# TouringMachineA1.net
KiCad netlist of a schematic drawn in EAGLE
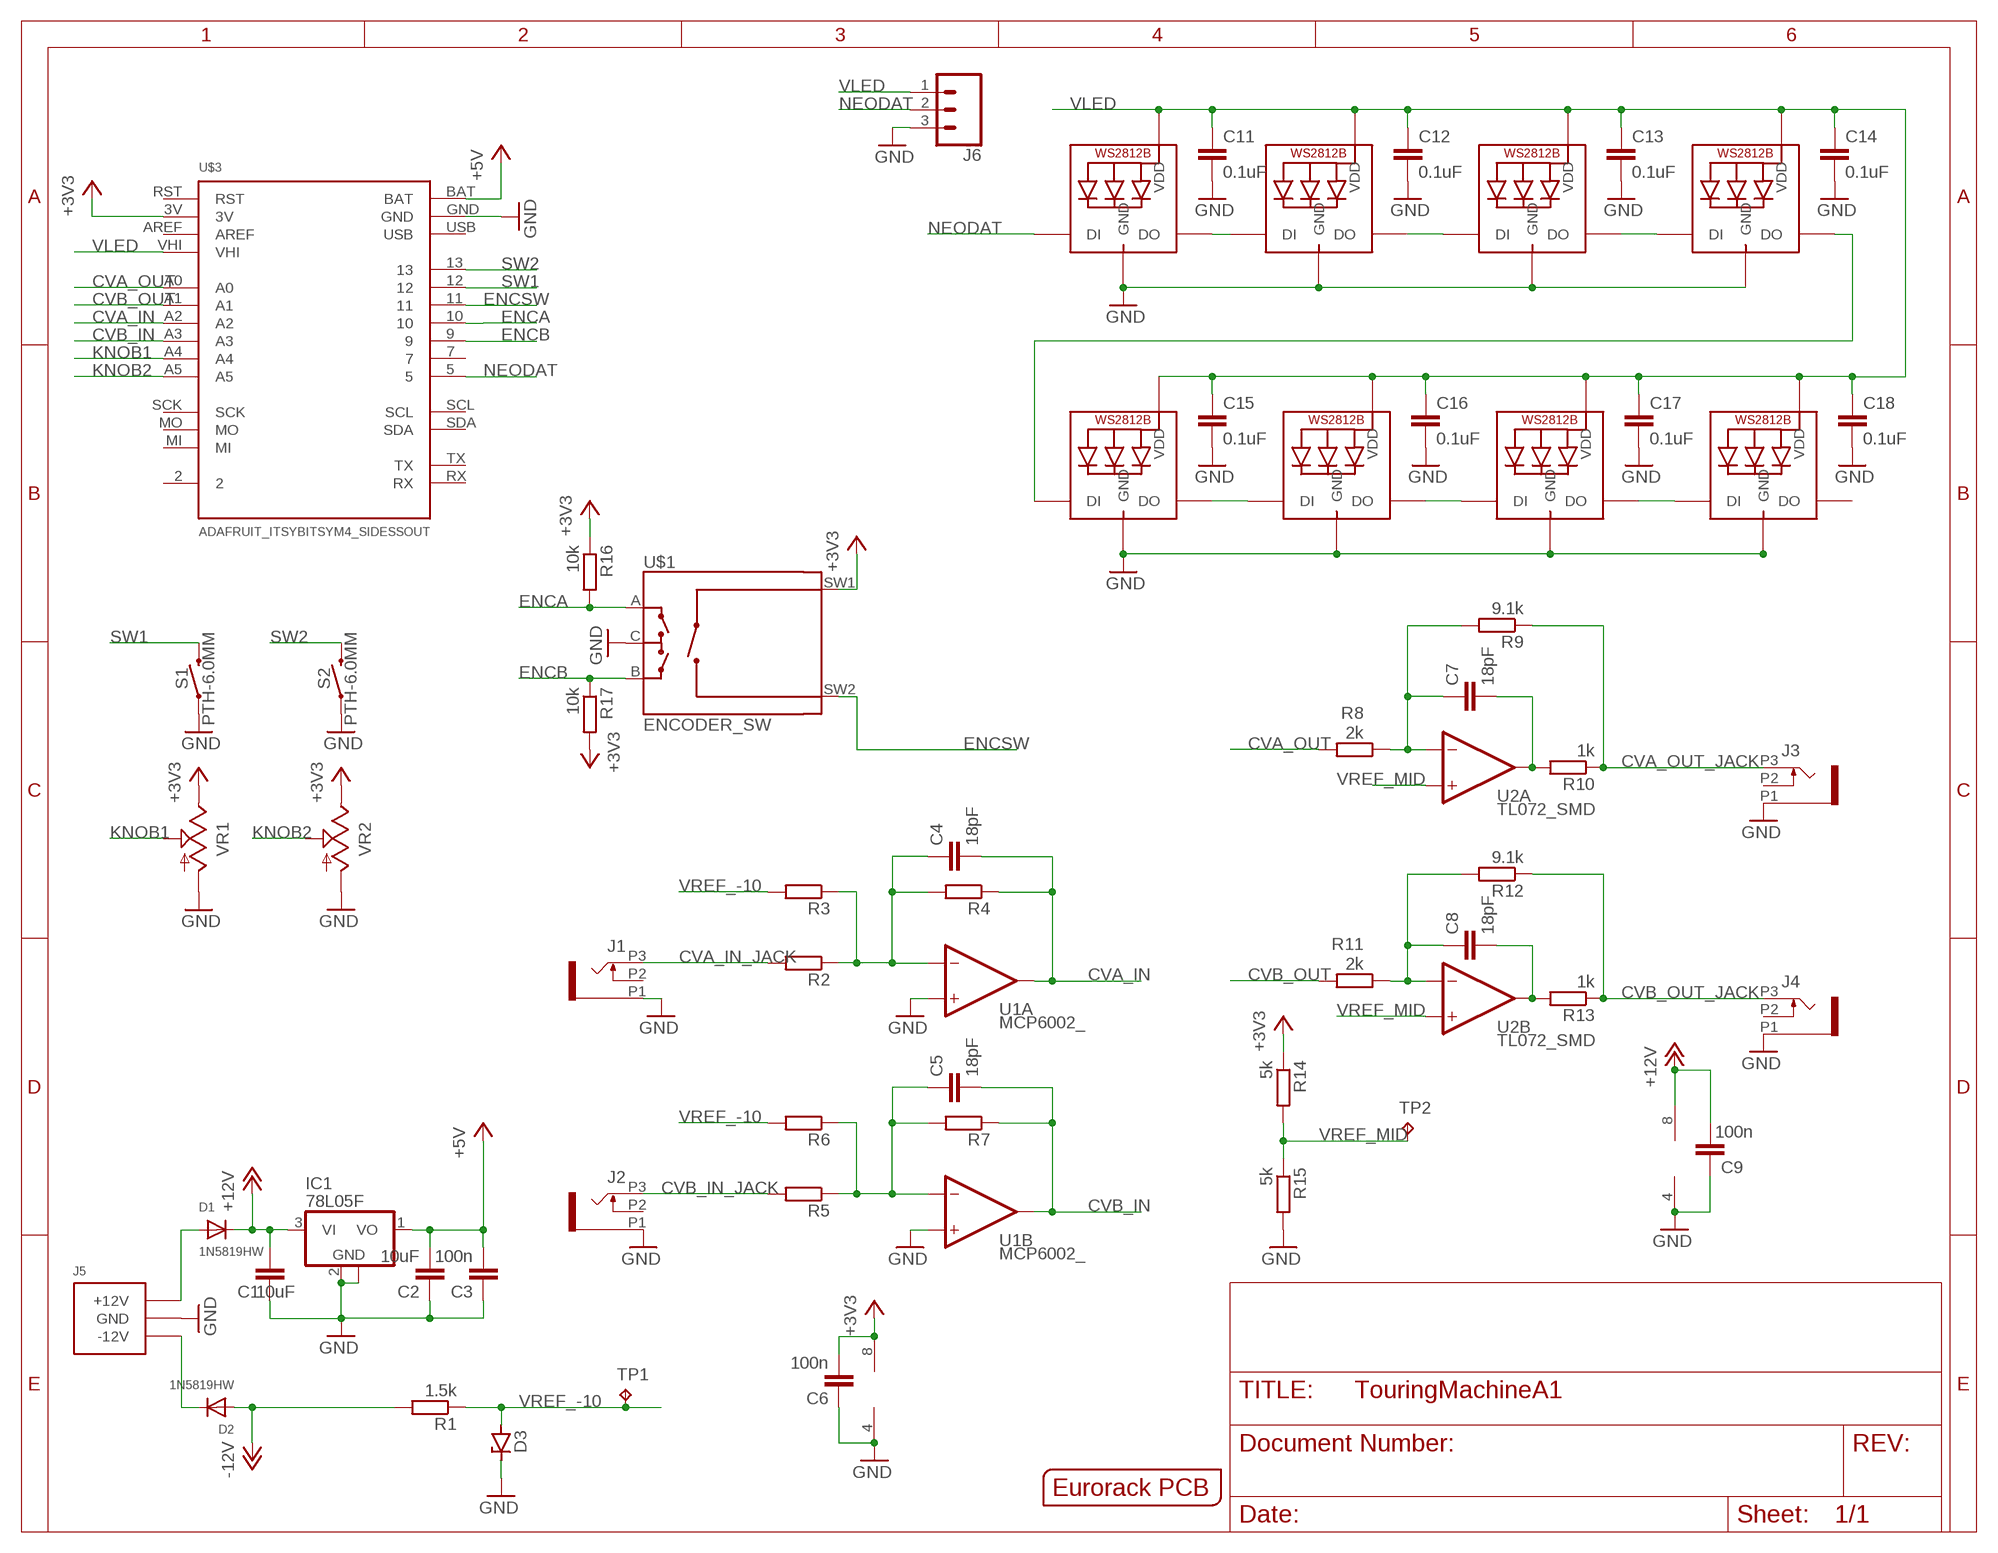
[diagram p0: schematic, sheet 1]

(export (version "E")
  (design (tool "Eeschema 10.0.6"))
  (components
    (comp (ref "C1")
      (value "10uF")
      (footprint "eagle-import:C0603")
      (libsource (lib "eagle-import") (part "C-EUC0603"))
    )
    (comp (ref "C2")
      (value "10uF")
      (footprint "eagle-import:C0603")
      (libsource (lib "eagle-import") (part "C-EUC0603"))
    )
    (comp (ref "C3")
      (value "100n")
      (footprint "eagle-import:C0603")
      (libsource (lib "eagle-import") (part "C-EUC0603"))
    )
    (comp (ref "C4")
      (value "18pF")
      (footprint "eagle-import:C0603")
      (libsource (lib "eagle-import") (part "C-EUC0603"))
    )
    (comp (ref "C5")
      (value "18pF")
      (footprint "eagle-import:C0603")
      (libsource (lib "eagle-import") (part "C-EUC0603"))
    )
    (comp (ref "C6")
      (value "100n")
      (footprint "eagle-import:C0603")
      (libsource (lib "eagle-import") (part "C-EUC0603"))
    )
    (comp (ref "C7")
      (value "18pF")
      (footprint "eagle-import:C0603")
      (libsource (lib "eagle-import") (part "C-EUC0603"))
    )
    (comp (ref "C8")
      (value "18pF")
      (footprint "eagle-import:C0603")
      (libsource (lib "eagle-import") (part "C-EUC0603"))
    )
    (comp (ref "C9")
      (value "100n")
      (footprint "eagle-import:C0603")
      (libsource (lib "eagle-import") (part "C-EUC0603"))
    )
    (comp (ref "C11")
      (value "0.1uF")
      (footprint "eagle-import:C0603")
      (libsource (lib "eagle-import") (part "C-EUC0603"))
    )
    (comp (ref "C12")
      (value "0.1uF")
      (footprint "eagle-import:C0603")
      (libsource (lib "eagle-import") (part "C-EUC0603"))
    )
    (comp (ref "C13")
      (value "0.1uF")
      (footprint "eagle-import:C0603")
      (libsource (lib "eagle-import") (part "C-EUC0603"))
    )
    (comp (ref "C14")
      (value "0.1uF")
      (footprint "eagle-import:C0603")
      (libsource (lib "eagle-import") (part "C-EUC0603"))
    )
    (comp (ref "C15")
      (value "0.1uF")
      (footprint "eagle-import:C0603")
      (libsource (lib "eagle-import") (part "C-EUC0603"))
    )
    (comp (ref "C16")
      (value "0.1uF")
      (footprint "eagle-import:C0603")
      (libsource (lib "eagle-import") (part "C-EUC0603"))
    )
    (comp (ref "C17")
      (value "0.1uF")
      (footprint "eagle-import:C0603")
      (libsource (lib "eagle-import") (part "C-EUC0603"))
    )
    (comp (ref "C18")
      (value "0.1uF")
      (footprint "eagle-import:C0603")
      (libsource (lib "eagle-import") (part "C-EUC0603"))
    )
    (comp (ref "D1")
      (value "1N5819HW")
      (footprint "eagle-import:SOD-123")
      (libsource (lib "eagle-import") (part "DIODESOD-123"))
    )
    (comp (ref "D2")
      (value "1N5819HW")
      (footprint "eagle-import:SOD-123")
      (libsource (lib "eagle-import") (part "DIODESOD-123"))
    )
    (comp (ref "D3")
      (value "ZENER-DIODESOT23")
      (footprint "eagle-import:SOT23")
      (libsource (lib "eagle-import") (part "ZENER-DIODESOT23"))
    )
    (comp (ref "IC1")
      (value "78L05F")
      (footprint "eagle-import:SOT89")
      (libsource (lib "eagle-import") (part "78LF05"))
    )
    (comp (ref "J1")
      (value "PJ301_THONKICONN6")
      (footprint "eagle-import:WQP_PJ_301M6")
      (libsource (lib "eagle-import") (part "PJ301_THONKICONN6"))
    )
    (comp (ref "J2")
      (value "PJ301_THONKICONN6")
      (footprint "eagle-import:WQP_PJ_301M6")
      (libsource (lib "eagle-import") (part "PJ301_THONKICONN6"))
    )
    (comp (ref "J3")
      (value "PJ301_THONKICONN6")
      (footprint "eagle-import:WQP_PJ_301M6")
      (libsource (lib "eagle-import") (part "PJ301_THONKICONN6"))
    )
    (comp (ref "J4")
      (value "PJ301_THONKICONN6")
      (footprint "eagle-import:WQP_PJ_301M6")
      (libsource (lib "eagle-import") (part "PJ301_THONKICONN6"))
    )
    (comp (ref "J5")
      (value "POWER_SIMPLE10-OTHERSIDE")
      (footprint "eagle-import:POWER_10_LABELSOTHERSIDE")
      (libsource (lib "eagle-import") (part "POWER_SIMPLE10-OTHERSIDE"))
    )
    (comp (ref "J6")
      (value "CONN_03")
      (footprint "eagle-import:1X03")
      (libsource (lib "eagle-import") (part "CONN_03"))
    )
    (comp (ref "LED1")
      (value "WS2812B5050")
      (footprint "eagle-import:WS2812B")
      (libsource (lib "eagle-import") (part "WS2812B5050"))
    )
    (comp (ref "LED2")
      (value "WS2812B5050")
      (footprint "eagle-import:WS2812B")
      (libsource (lib "eagle-import") (part "WS2812B5050"))
    )
    (comp (ref "LED3")
      (value "WS2812B5050")
      (footprint "eagle-import:WS2812B")
      (libsource (lib "eagle-import") (part "WS2812B5050"))
    )
    (comp (ref "LED4")
      (value "WS2812B5050")
      (footprint "eagle-import:WS2812B")
      (libsource (lib "eagle-import") (part "WS2812B5050"))
    )
    (comp (ref "LED5")
      (value "WS2812B5050")
      (footprint "eagle-import:WS2812B")
      (libsource (lib "eagle-import") (part "WS2812B5050"))
    )
    (comp (ref "LED6")
      (value "WS2812B5050")
      (footprint "eagle-import:WS2812B")
      (libsource (lib "eagle-import") (part "WS2812B5050"))
    )
    (comp (ref "LED7")
      (value "WS2812B5050")
      (footprint "eagle-import:WS2812B")
      (libsource (lib "eagle-import") (part "WS2812B5050"))
    )
    (comp (ref "LED8")
      (value "WS2812B5050")
      (footprint "eagle-import:WS2812B")
      (libsource (lib "eagle-import") (part "WS2812B5050"))
    )
    (comp (ref "PCB1")
      (value "EURORACK_PCB6HP")
      (footprint "eagle-import:EURORACK6HPPCB")
      (libsource (lib "eagle-import") (part "EURORACK_PCB6HP"))
    )
    (comp (ref "R1")
      (value "1.5k")
      (footprint "eagle-import:R0603")
      (libsource (lib "eagle-import") (part "R-EU_R0603"))
    )
    (comp (ref "R2")
      (value "R-EU_R0603")
      (footprint "eagle-import:R0603")
      (libsource (lib "eagle-import") (part "R-EU_R0603"))
    )
    (comp (ref "R3")
      (value "R-EU_R0603")
      (footprint "eagle-import:R0603")
      (libsource (lib "eagle-import") (part "R-EU_R0603"))
    )
    (comp (ref "R4")
      (value "R-EU_R0603")
      (footprint "eagle-import:R0603")
      (libsource (lib "eagle-import") (part "R-EU_R0603"))
    )
    (comp (ref "R5")
      (value "R-EU_R0603")
      (footprint "eagle-import:R0603")
      (libsource (lib "eagle-import") (part "R-EU_R0603"))
    )
    (comp (ref "R6")
      (value "R-EU_R0603")
      (footprint "eagle-import:R0603")
      (libsource (lib "eagle-import") (part "R-EU_R0603"))
    )
    (comp (ref "R7")
      (value "R-EU_R0603")
      (footprint "eagle-import:R0603")
      (libsource (lib "eagle-import") (part "R-EU_R0603"))
    )
    (comp (ref "R8")
      (value "2k")
      (footprint "eagle-import:R0603")
      (libsource (lib "eagle-import") (part "R-EU_R0603"))
    )
    (comp (ref "R9")
      (value "9.1k")
      (footprint "eagle-import:R0603")
      (libsource (lib "eagle-import") (part "R-EU_R0603"))
    )
    (comp (ref "R10")
      (value "1k")
      (footprint "eagle-import:R0603")
      (libsource (lib "eagle-import") (part "R-EU_R0603"))
    )
    (comp (ref "R11")
      (value "2k")
      (footprint "eagle-import:R0603")
      (libsource (lib "eagle-import") (part "R-EU_R0603"))
    )
    (comp (ref "R12")
      (value "9.1k")
      (footprint "eagle-import:R0603")
      (libsource (lib "eagle-import") (part "R-EU_R0603"))
    )
    (comp (ref "R13")
      (value "1k")
      (footprint "eagle-import:R0603")
      (libsource (lib "eagle-import") (part "R-EU_R0603"))
    )
    (comp (ref "R14")
      (value "5k")
      (footprint "eagle-import:R0603")
      (libsource (lib "eagle-import") (part "R-EU_R0603"))
    )
    (comp (ref "R15")
      (value "5k")
      (footprint "eagle-import:R0603")
      (libsource (lib "eagle-import") (part "R-EU_R0603"))
    )
    (comp (ref "R16")
      (value "10k")
      (footprint "eagle-import:R0603")
      (libsource (lib "eagle-import") (part "R-EU_R0603"))
    )
    (comp (ref "R17")
      (value "10k")
      (footprint "eagle-import:R0603")
      (libsource (lib "eagle-import") (part "R-EU_R0603"))
    )
    (comp (ref "S1")
      (value "PTH-6.0MM")
      (footprint "eagle-import:TACTILE_SWITCH_PTH_6.0MM")
      (libsource (lib "eagle-import") (part "MOMENTARY-SWITCH-SPST-PTH-6.0MM"))
    )
    (comp (ref "S2")
      (value "PTH-6.0MM")
      (footprint "eagle-import:TACTILE_SWITCH_PTH_6.0MM")
      (libsource (lib "eagle-import") (part "MOMENTARY-SWITCH-SPST-PTH-6.0MM"))
    )
    (comp (ref "TP1")
      (value "TPTP15R")
      (footprint "eagle-import:TP15R")
      (libsource (lib "eagle-import") (part "TPTP15R"))
    )
    (comp (ref "TP2")
      (value "TPTP15R")
      (footprint "eagle-import:TP15R")
      (libsource (lib "eagle-import") (part "TPTP15R"))
    )
    (comp (ref "U$1")
      (value "ENCODER_SW")
      (footprint "eagle-import:ENCODER_SW")
      (libsource (lib "eagle-import") (part "ENCODER_SW"))
    )
    (comp (ref "U$3")
      (value "ADAFRUIT_ITSYBITSYM4_SIDESSOUT")
      (footprint "eagle-import:ADAFRUIT_ITSYBITSYM4_SIDESOUT")
      (libsource (lib "eagle-import") (part "ADAFRUIT_ITSYBITSYM4_SIDESSOUT"))
    )
    (comp (ref "U1")
      (value "MCP6002_")
      (footprint "eagle-import:SO08")
      (libsource (lib "eagle-import") (part "MCP6002_"))
    )
    (comp (ref "U2")
      (value "TL072_SMD")
      (footprint "eagle-import:SO08")
      (libsource (lib "eagle-import") (part "TL072_SMD"))
    )
    (comp (ref "VR1")
      (value "9MM_SNAP-IN_POT_")
      (footprint "eagle-import:9MM_SNAP-IN_POT")
      (libsource (lib "eagle-import") (part "9MM_SNAP-IN_POT_"))
    )
    (comp (ref "VR2")
      (value "9MM_SNAP-IN_POT_")
      (footprint "eagle-import:9MM_SNAP-IN_POT")
      (libsource (lib "eagle-import") (part "9MM_SNAP-IN_POT_"))
    )
  )
  (nets
    (net (code "1") (name "+3V3") (class "Default")
      (node (ref "C6") (pin "2") (pinfunction "2_2") (pintype "passive"))
      (node (ref "R14") (pin "1") (pinfunction "1_1") (pintype "passive"))
      (node (ref "R16") (pin "1") (pinfunction "1_1") (pintype "passive"))
      (node (ref "R17") (pin "2") (pinfunction "2_2") (pintype "passive"))
      (node (ref "U$1") (pin "SW1") (pinfunction "SW1_SW1") (pintype "passive"))
      (node (ref "U$3") (pin "3V") (pinfunction "3V_3V") (pintype "bidirectional"))
      (node (ref "U1") (pin "8") (pinfunction "V+_8") (pintype "power_in"))
      (node (ref "VR1") (pin "3") (pinfunction "E_3") (pintype "passive"))
      (node (ref "VR2") (pin "3") (pinfunction "E_3") (pintype "passive"))
    )
    (net (code "2") (name "+5V") (class "Default")
      (node (ref "C2") (pin "2") (pinfunction "2_2") (pintype "passive"))
      (node (ref "C3") (pin "2") (pinfunction "2_2") (pintype "passive"))
      (node (ref "IC1") (pin "1") (pinfunction "VO_1") (pintype "passive"))
      (node (ref "U$3") (pin "BAT") (pinfunction "BAT_BAT") (pintype "bidirectional"))
    )
    (net (code "3") (name "+12V") (class "Default")
      (node (ref "C1") (pin "2") (pinfunction "2_2") (pintype "passive"))
      (node (ref "C9") (pin "2") (pinfunction "2_2") (pintype "passive"))
      (node (ref "D1") (pin "C") (pinfunction "C_C") (pintype "passive"))
      (node (ref "IC1") (pin "3") (pinfunction "VI_3") (pintype "input"))
      (node (ref "U2") (pin "8") (pinfunction "V+_8") (pintype "power_in"))
    )
    (net (code "4") (name "-12V") (class "Default")
      (node (ref "D2") (pin "A") (pinfunction "A_A") (pintype "passive"))
      (node (ref "R1") (pin "2") (pinfunction "2_2") (pintype "passive"))
    )
    (net (code "5") (name "/CVA_IN") (class "Default")
      (node (ref "C4") (pin "2") (pinfunction "2_2") (pintype "passive"))
      (node (ref "R4") (pin "1") (pinfunction "1_1") (pintype "passive"))
      (node (ref "U$3") (pin "A2") (pinfunction "A2_A2") (pintype "bidirectional"))
      (node (ref "U1") (pin "1") (pinfunction "OUT_1") (pintype "output"))
    )
    (net (code "6") (name "/CVA_IN_JACK") (class "Default")
      (node (ref "J1") (pin "P3") (pinfunction "3_P3") (pintype "passive"))
      (node (ref "R2") (pin "2") (pinfunction "2_2") (pintype "passive"))
    )
    (net (code "7") (name "/CVA_OUT") (class "Default")
      (node (ref "R8") (pin "2") (pinfunction "2_2") (pintype "passive"))
      (node (ref "U$3") (pin "A0") (pinfunction "A0_A0") (pintype "bidirectional"))
    )
    (net (code "8") (name "/CVA_OUT_JACK") (class "Default")
      (node (ref "J3") (pin "P3") (pinfunction "3_P3") (pintype "passive"))
      (node (ref "R10") (pin "1") (pinfunction "1_1") (pintype "passive"))
      (node (ref "R9") (pin "1") (pinfunction "1_1") (pintype "passive"))
    )
    (net (code "9") (name "/CVB_IN") (class "Default")
      (node (ref "C5") (pin "2") (pinfunction "2_2") (pintype "passive"))
      (node (ref "R7") (pin "1") (pinfunction "1_1") (pintype "passive"))
      (node (ref "U$3") (pin "A3") (pinfunction "A3_A3") (pintype "bidirectional"))
      (node (ref "U1") (pin "7") (pinfunction "OUT_7") (pintype "output"))
    )
    (net (code "10") (name "/CVB_IN_JACK") (class "Default")
      (node (ref "J2") (pin "P3") (pinfunction "3_P3") (pintype "passive"))
      (node (ref "R5") (pin "2") (pinfunction "2_2") (pintype "passive"))
    )
    (net (code "11") (name "/CVB_OUT") (class "Default")
      (node (ref "R11") (pin "2") (pinfunction "2_2") (pintype "passive"))
      (node (ref "U$3") (pin "A1") (pinfunction "A1_A1") (pintype "bidirectional"))
    )
    (net (code "12") (name "/CVB_OUT_JACK") (class "Default")
      (node (ref "J4") (pin "P3") (pinfunction "3_P3") (pintype "passive"))
      (node (ref "R12") (pin "1") (pinfunction "1_1") (pintype "passive"))
      (node (ref "R13") (pin "1") (pinfunction "1_1") (pintype "passive"))
    )
    (net (code "13") (name "/ENCA") (class "Default")
      (node (ref "R16") (pin "2") (pinfunction "2_2") (pintype "passive"))
      (node (ref "U$1") (pin "A") (pinfunction "A_A") (pintype "bidirectional"))
      (node (ref "U$3") (pin "10") (pinfunction "10_10") (pintype "bidirectional"))
    )
    (net (code "14") (name "/ENCB") (class "Default")
      (node (ref "R17") (pin "1") (pinfunction "1_1") (pintype "passive"))
      (node (ref "U$1") (pin "B") (pinfunction "B_B") (pintype "bidirectional"))
      (node (ref "U$3") (pin "9") (pinfunction "9_9") (pintype "bidirectional"))
    )
    (net (code "15") (name "/ENCSW") (class "Default")
      (node (ref "U$1") (pin "SW2") (pinfunction "SW2_SW2") (pintype "passive"))
      (node (ref "U$3") (pin "11") (pinfunction "11_11") (pintype "bidirectional"))
    )
    (net (code "16") (name "/KNOB1") (class "Default")
      (node (ref "U$3") (pin "A4") (pinfunction "A4_A4") (pintype "bidirectional"))
      (node (ref "VR1") (pin "2") (pinfunction "S_2") (pintype "passive"))
    )
    (net (code "17") (name "/KNOB2") (class "Default")
      (node (ref "U$3") (pin "A5") (pinfunction "A5_A5") (pintype "bidirectional"))
      (node (ref "VR2") (pin "2") (pinfunction "S_2") (pintype "passive"))
    )
    (net (code "18") (name "/NEODAT") (class "Default")
      (node (ref "J6") (pin "2") (pinfunction "2_2") (pintype "passive"))
      (node (ref "LED1") (pin "4-DIN") (pinfunction "DI_4-DIN") (pintype "input"))
      (node (ref "U$3") (pin "5") (pinfunction "5_5") (pintype "bidirectional"))
    )
    (net (code "19") (name "/SW1") (class "Default")
      (node (ref "S1") (pin "3") (pinfunction "2_3") (pintype "passive"))
      (node (ref "U$3") (pin "12") (pinfunction "12_12") (pintype "bidirectional"))
    )
    (net (code "20") (name "/SW2") (class "Default")
      (node (ref "S2") (pin "3") (pinfunction "2_3") (pintype "passive"))
      (node (ref "U$3") (pin "13") (pinfunction "13_13") (pintype "bidirectional"))
    )
    (net (code "21") (name "/VLED") (class "Default")
      (node (ref "C11") (pin "1") (pinfunction "1_1") (pintype "passive"))
      (node (ref "C12") (pin "1") (pinfunction "1_1") (pintype "passive"))
      (node (ref "C13") (pin "1") (pinfunction "1_1") (pintype "passive"))
      (node (ref "C14") (pin "1") (pinfunction "1_1") (pintype "passive"))
      (node (ref "C15") (pin "1") (pinfunction "1_1") (pintype "passive"))
      (node (ref "C16") (pin "1") (pinfunction "1_1") (pintype "passive"))
      (node (ref "C17") (pin "1") (pinfunction "1_1") (pintype "passive"))
      (node (ref "C18") (pin "1") (pinfunction "1_1") (pintype "passive"))
      (node (ref "J6") (pin "1") (pinfunction "1_1") (pintype "passive"))
      (node (ref "LED1") (pin "1-VDD") (pinfunction "VDD_1-VDD") (pintype "power_in"))
      (node (ref "LED2") (pin "1-VDD") (pinfunction "VDD_1-VDD") (pintype "power_in"))
      (node (ref "LED3") (pin "1-VDD") (pinfunction "VDD_1-VDD") (pintype "power_in"))
      (node (ref "LED4") (pin "1-VDD") (pinfunction "VDD_1-VDD") (pintype "power_in"))
      (node (ref "LED5") (pin "1-VDD") (pinfunction "VDD_1-VDD") (pintype "power_in"))
      (node (ref "LED6") (pin "1-VDD") (pinfunction "VDD_1-VDD") (pintype "power_in"))
      (node (ref "LED7") (pin "1-VDD") (pinfunction "VDD_1-VDD") (pintype "power_in"))
      (node (ref "LED8") (pin "1-VDD") (pinfunction "VDD_1-VDD") (pintype "power_in"))
      (node (ref "U$3") (pin "VHI") (pinfunction "VHI_VHI") (pintype "bidirectional"))
    )
    (net (code "22") (name "/VREF_-10") (class "Default")
      (node (ref "D3") (pin "1") (pinfunction "A_1") (pintype "passive"))
      (node (ref "R1") (pin "1") (pinfunction "1_1") (pintype "passive"))
      (node (ref "R3") (pin "2") (pinfunction "2_2") (pintype "passive"))
      (node (ref "R6") (pin "2") (pinfunction "2_2") (pintype "passive"))
      (node (ref "TP1") (pin "TP") (pinfunction "TP_TP") (pintype "input"))
    )
    (net (code "23") (name "/VREF_MID") (class "Default")
      (node (ref "R14") (pin "2") (pinfunction "2_2") (pintype "passive"))
      (node (ref "R15") (pin "1") (pinfunction "1_1") (pintype "passive"))
      (node (ref "TP2") (pin "TP") (pinfunction "TP_TP") (pintype "input"))
      (node (ref "U2") (pin "3") (pinfunction "+IN_3") (pintype "input"))
      (node (ref "U2") (pin "5") (pinfunction "+IN_5") (pintype "input"))
    )
    (net (code "24") (name "GND") (class "Default")
      (node (ref "C1") (pin "1") (pinfunction "1_1") (pintype "passive"))
      (node (ref "C11") (pin "2") (pinfunction "2_2") (pintype "passive"))
      (node (ref "C12") (pin "2") (pinfunction "2_2") (pintype "passive"))
      (node (ref "C13") (pin "2") (pinfunction "2_2") (pintype "passive"))
      (node (ref "C14") (pin "2") (pinfunction "2_2") (pintype "passive"))
      (node (ref "C15") (pin "2") (pinfunction "2_2") (pintype "passive"))
      (node (ref "C16") (pin "2") (pinfunction "2_2") (pintype "passive"))
      (node (ref "C17") (pin "2") (pinfunction "2_2") (pintype "passive"))
      (node (ref "C18") (pin "2") (pinfunction "2_2") (pintype "passive"))
      (node (ref "C2") (pin "1") (pinfunction "1_1") (pintype "passive"))
      (node (ref "C3") (pin "1") (pinfunction "1_1") (pintype "passive"))
      (node (ref "C6") (pin "1") (pinfunction "1_1") (pintype "passive"))
      (node (ref "C9") (pin "1") (pinfunction "1_1") (pintype "passive"))
      (node (ref "D3") (pin "3") (pinfunction "C_3") (pintype "passive"))
      (node (ref "IC1") (pin "2") (pinfunction "GND_2") (pintype "passive"))
      (node (ref "IC1") (pin "2@1") (pinfunction "GND_2@1") (pintype "passive"))
      (node (ref "J1") (pin "P1") (pinfunction "1_P1") (pintype "passive"))
      (node (ref "J2") (pin "P1") (pinfunction "1_P1") (pintype "passive"))
      (node (ref "J3") (pin "P1") (pinfunction "1_P1") (pintype "passive"))
      (node (ref "J4") (pin "P1") (pinfunction "1_P1") (pintype "passive"))
      (node (ref "J5") (pin "3") (pinfunction "GND_3") (pintype "bidirectional"))
      (node (ref "J5") (pin "4") (pinfunction "GND_4") (pintype "bidirectional"))
      (node (ref "J5") (pin "5") (pinfunction "GND_5") (pintype "bidirectional"))
      (node (ref "J5") (pin "6") (pinfunction "GND_6") (pintype "bidirectional"))
      (node (ref "J5") (pin "7") (pinfunction "GND_7") (pintype "bidirectional"))
      (node (ref "J5") (pin "8") (pinfunction "GND_8") (pintype "bidirectional"))
      (node (ref "J6") (pin "3") (pinfunction "3_3") (pintype "passive"))
      (node (ref "LED1") (pin "3-GND") (pinfunction "GND_3-GND") (pintype "power_in"))
      (node (ref "LED2") (pin "3-GND") (pinfunction "GND_3-GND") (pintype "power_in"))
      (node (ref "LED3") (pin "3-GND") (pinfunction "GND_3-GND") (pintype "power_in"))
      (node (ref "LED4") (pin "3-GND") (pinfunction "GND_3-GND") (pintype "power_in"))
      (node (ref "LED5") (pin "3-GND") (pinfunction "GND_3-GND") (pintype "power_in"))
      (node (ref "LED6") (pin "3-GND") (pinfunction "GND_3-GND") (pintype "power_in"))
      (node (ref "LED7") (pin "3-GND") (pinfunction "GND_3-GND") (pintype "power_in"))
      (node (ref "LED8") (pin "3-GND") (pinfunction "GND_3-GND") (pintype "power_in"))
      (node (ref "R15") (pin "2") (pinfunction "2_2") (pintype "passive"))
      (node (ref "S1") (pin "1") (pinfunction "1_1") (pintype "passive"))
      (node (ref "S2") (pin "1") (pinfunction "1_1") (pintype "passive"))
      (node (ref "U$1") (pin "C") (pinfunction "C_C") (pintype "bidirectional"))
      (node (ref "U$3") (pin "GND") (pinfunction "GND_GND") (pintype "bidirectional"))
      (node (ref "U1") (pin "3") (pinfunction "+IN_3") (pintype "input"))
      (node (ref "U1") (pin "4") (pinfunction "V-_4") (pintype "power_in"))
      (node (ref "U1") (pin "5") (pinfunction "+IN_5") (pintype "input"))
      (node (ref "U2") (pin "4") (pinfunction "V-_4") (pintype "power_in"))
      (node (ref "VR1") (pin "1") (pinfunction "A_1") (pintype "passive"))
      (node (ref "VR2") (pin "1") (pinfunction "A_1") (pintype "passive"))
    )
    (net (code "25") (name "Net-(D1-PadA)") (class "Default")
      (node (ref "D1") (pin "A") (pinfunction "A_A") (pintype "passive"))
      (node (ref "J5") (pin "10") (pinfunction "+12V_10") (pintype "bidirectional"))
      (node (ref "J5") (pin "9") (pinfunction "+12V_9") (pintype "bidirectional"))
    )
    (net (code "26") (name "Net-(D2-PadC)") (class "Default")
      (node (ref "D2") (pin "C") (pinfunction "C_C") (pintype "passive"))
      (node (ref "J5") (pin "1") (pinfunction "-12V_1") (pintype "bidirectional"))
      (node (ref "J5") (pin "2") (pinfunction "-12V_2") (pintype "bidirectional"))
    )
    (net (code "27") (name "Net-(LED1-DO)") (class "Default")
      (node (ref "LED1") (pin "2-DOUT") (pinfunction "DO_2-DOUT") (pintype "output"))
      (node (ref "LED2") (pin "4-DIN") (pinfunction "DI_4-DIN") (pintype "input"))
    )
    (net (code "28") (name "Net-(LED2-DO)") (class "Default")
      (node (ref "LED2") (pin "2-DOUT") (pinfunction "DO_2-DOUT") (pintype "output"))
      (node (ref "LED3") (pin "4-DIN") (pinfunction "DI_4-DIN") (pintype "input"))
    )
    (net (code "29") (name "Net-(LED3-DO)") (class "Default")
      (node (ref "LED3") (pin "2-DOUT") (pinfunction "DO_2-DOUT") (pintype "output"))
      (node (ref "LED4") (pin "4-DIN") (pinfunction "DI_4-DIN") (pintype "input"))
    )
    (net (code "30") (name "Net-(LED4-DO)") (class "Default")
      (node (ref "LED4") (pin "2-DOUT") (pinfunction "DO_2-DOUT") (pintype "output"))
      (node (ref "LED5") (pin "4-DIN") (pinfunction "DI_4-DIN") (pintype "input"))
    )
    (net (code "31") (name "Net-(LED5-DO)") (class "Default")
      (node (ref "LED5") (pin "2-DOUT") (pinfunction "DO_2-DOUT") (pintype "output"))
      (node (ref "LED6") (pin "4-DIN") (pinfunction "DI_4-DIN") (pintype "input"))
    )
    (net (code "32") (name "Net-(LED6-DO)") (class "Default")
      (node (ref "LED6") (pin "2-DOUT") (pinfunction "DO_2-DOUT") (pintype "output"))
      (node (ref "LED7") (pin "4-DIN") (pinfunction "DI_4-DIN") (pintype "input"))
    )
    (net (code "33") (name "Net-(LED7-DO)") (class "Default")
      (node (ref "LED7") (pin "2-DOUT") (pinfunction "DO_2-DOUT") (pintype "output"))
      (node (ref "LED8") (pin "4-DIN") (pinfunction "DI_4-DIN") (pintype "input"))
    )
    (net (code "34") (name "Net-(U1A--IN)") (class "Default")
      (node (ref "C4") (pin "1") (pinfunction "1_1") (pintype "passive"))
      (node (ref "R2") (pin "1") (pinfunction "1_1") (pintype "passive"))
      (node (ref "R3") (pin "1") (pinfunction "1_1") (pintype "passive"))
      (node (ref "R4") (pin "2") (pinfunction "2_2") (pintype "passive"))
      (node (ref "U1") (pin "2") (pinfunction "-IN_2") (pintype "input"))
    )
    (net (code "35") (name "Net-(U1B--IN)") (class "Default")
      (node (ref "C5") (pin "1") (pinfunction "1_1") (pintype "passive"))
      (node (ref "R5") (pin "1") (pinfunction "1_1") (pintype "passive"))
      (node (ref "R6") (pin "1") (pinfunction "1_1") (pintype "passive"))
      (node (ref "R7") (pin "2") (pinfunction "2_2") (pintype "passive"))
      (node (ref "U1") (pin "6") (pinfunction "-IN_6") (pintype "input"))
    )
    (net (code "36") (name "Net-(U2A--IN)") (class "Default")
      (node (ref "C7") (pin "1") (pinfunction "1_1") (pintype "passive"))
      (node (ref "R8") (pin "1") (pinfunction "1_1") (pintype "passive"))
      (node (ref "R9") (pin "2") (pinfunction "2_2") (pintype "passive"))
      (node (ref "U2") (pin "2") (pinfunction "-IN_2") (pintype "input"))
    )
    (net (code "37") (name "Net-(U2A-OUT)") (class "Default")
      (node (ref "C7") (pin "2") (pinfunction "2_2") (pintype "passive"))
      (node (ref "R10") (pin "2") (pinfunction "2_2") (pintype "passive"))
      (node (ref "U2") (pin "1") (pinfunction "OUT_1") (pintype "output"))
    )
    (net (code "38") (name "Net-(U2B--IN)") (class "Default")
      (node (ref "C8") (pin "1") (pinfunction "1_1") (pintype "passive"))
      (node (ref "R11") (pin "1") (pinfunction "1_1") (pintype "passive"))
      (node (ref "R12") (pin "2") (pinfunction "2_2") (pintype "passive"))
      (node (ref "U2") (pin "6") (pinfunction "-IN_6") (pintype "input"))
    )
    (net (code "39") (name "Net-(U2B-OUT)") (class "Default")
      (node (ref "C8") (pin "2") (pinfunction "2_2") (pintype "passive"))
      (node (ref "R13") (pin "2") (pinfunction "2_2") (pintype "passive"))
      (node (ref "U2") (pin "7") (pinfunction "OUT_7") (pintype "output"))
    )
    (net (code "40") (name "unconnected-(J1-2-PadP2)") (class "Default")
      (node (ref "J1") (pin "P2") (pinfunction "2_P2") (pintype "passive"))
    )
    (net (code "41") (name "unconnected-(J2-2-PadP2)") (class "Default")
      (node (ref "J2") (pin "P2") (pinfunction "2_P2") (pintype "passive"))
    )
    (net (code "42") (name "unconnected-(J3-2-PadP2)") (class "Default")
      (node (ref "J3") (pin "P2") (pinfunction "2_P2") (pintype "passive"))
    )
    (net (code "43") (name "unconnected-(J4-2-PadP2)") (class "Default")
      (node (ref "J4") (pin "P2") (pinfunction "2_P2") (pintype "passive"))
    )
    (net (code "44") (name "unconnected-(LED8-DO-Pad2-DOUT)") (class "Default")
      (node (ref "LED8") (pin "2-DOUT") (pinfunction "DO_2-DOUT") (pintype "output"))
    )
    (net (code "45") (name "unconnected-(U$3-Pad2)") (class "Default")
      (node (ref "U$3") (pin "2") (pinfunction "2_2") (pintype "bidirectional"))
    )
    (net (code "46") (name "unconnected-(U$3-Pad7)") (class "Default")
      (node (ref "U$3") (pin "7") (pinfunction "7_7") (pintype "bidirectional"))
    )
    (net (code "47") (name "unconnected-(U$3-PadAREF)") (class "Default")
      (node (ref "U$3") (pin "AREF") (pinfunction "AREF_AREF") (pintype "bidirectional"))
    )
    (net (code "48") (name "unconnected-(U$3-PadMI)") (class "Default")
      (node (ref "U$3") (pin "MI") (pinfunction "MI_MI") (pintype "bidirectional"))
    )
    (net (code "49") (name "unconnected-(U$3-PadMO)") (class "Default")
      (node (ref "U$3") (pin "MO") (pinfunction "MO_MO") (pintype "bidirectional"))
    )
    (net (code "50") (name "unconnected-(U$3-PadRST)") (class "Default")
      (node (ref "U$3") (pin "RST") (pinfunction "RST_RST") (pintype "bidirectional"))
    )
    (net (code "51") (name "unconnected-(U$3-PadRX)") (class "Default")
      (node (ref "U$3") (pin "RX") (pinfunction "RX_RX") (pintype "bidirectional"))
    )
    (net (code "52") (name "unconnected-(U$3-PadSCK)") (class "Default")
      (node (ref "U$3") (pin "SCK") (pinfunction "SCK_SCK") (pintype "bidirectional"))
    )
    (net (code "53") (name "unconnected-(U$3-PadSCL)") (class "Default")
      (node (ref "U$3") (pin "SCL") (pinfunction "SCL_SCL") (pintype "bidirectional"))
    )
    (net (code "54") (name "unconnected-(U$3-PadSDA)") (class "Default")
      (node (ref "U$3") (pin "SDA") (pinfunction "SDA_SDA") (pintype "bidirectional"))
    )
    (net (code "55") (name "unconnected-(U$3-PadTX)") (class "Default")
      (node (ref "U$3") (pin "TX") (pinfunction "TX_TX") (pintype "bidirectional"))
    )
    (net (code "56") (name "unconnected-(U$3-PadUSB)") (class "Default")
      (node (ref "U$3") (pin "USB") (pinfunction "USB_USB") (pintype "bidirectional"))
    )
  )
)
